# Main.net
KiCad netlist of a schematic drawn in Altium Designer
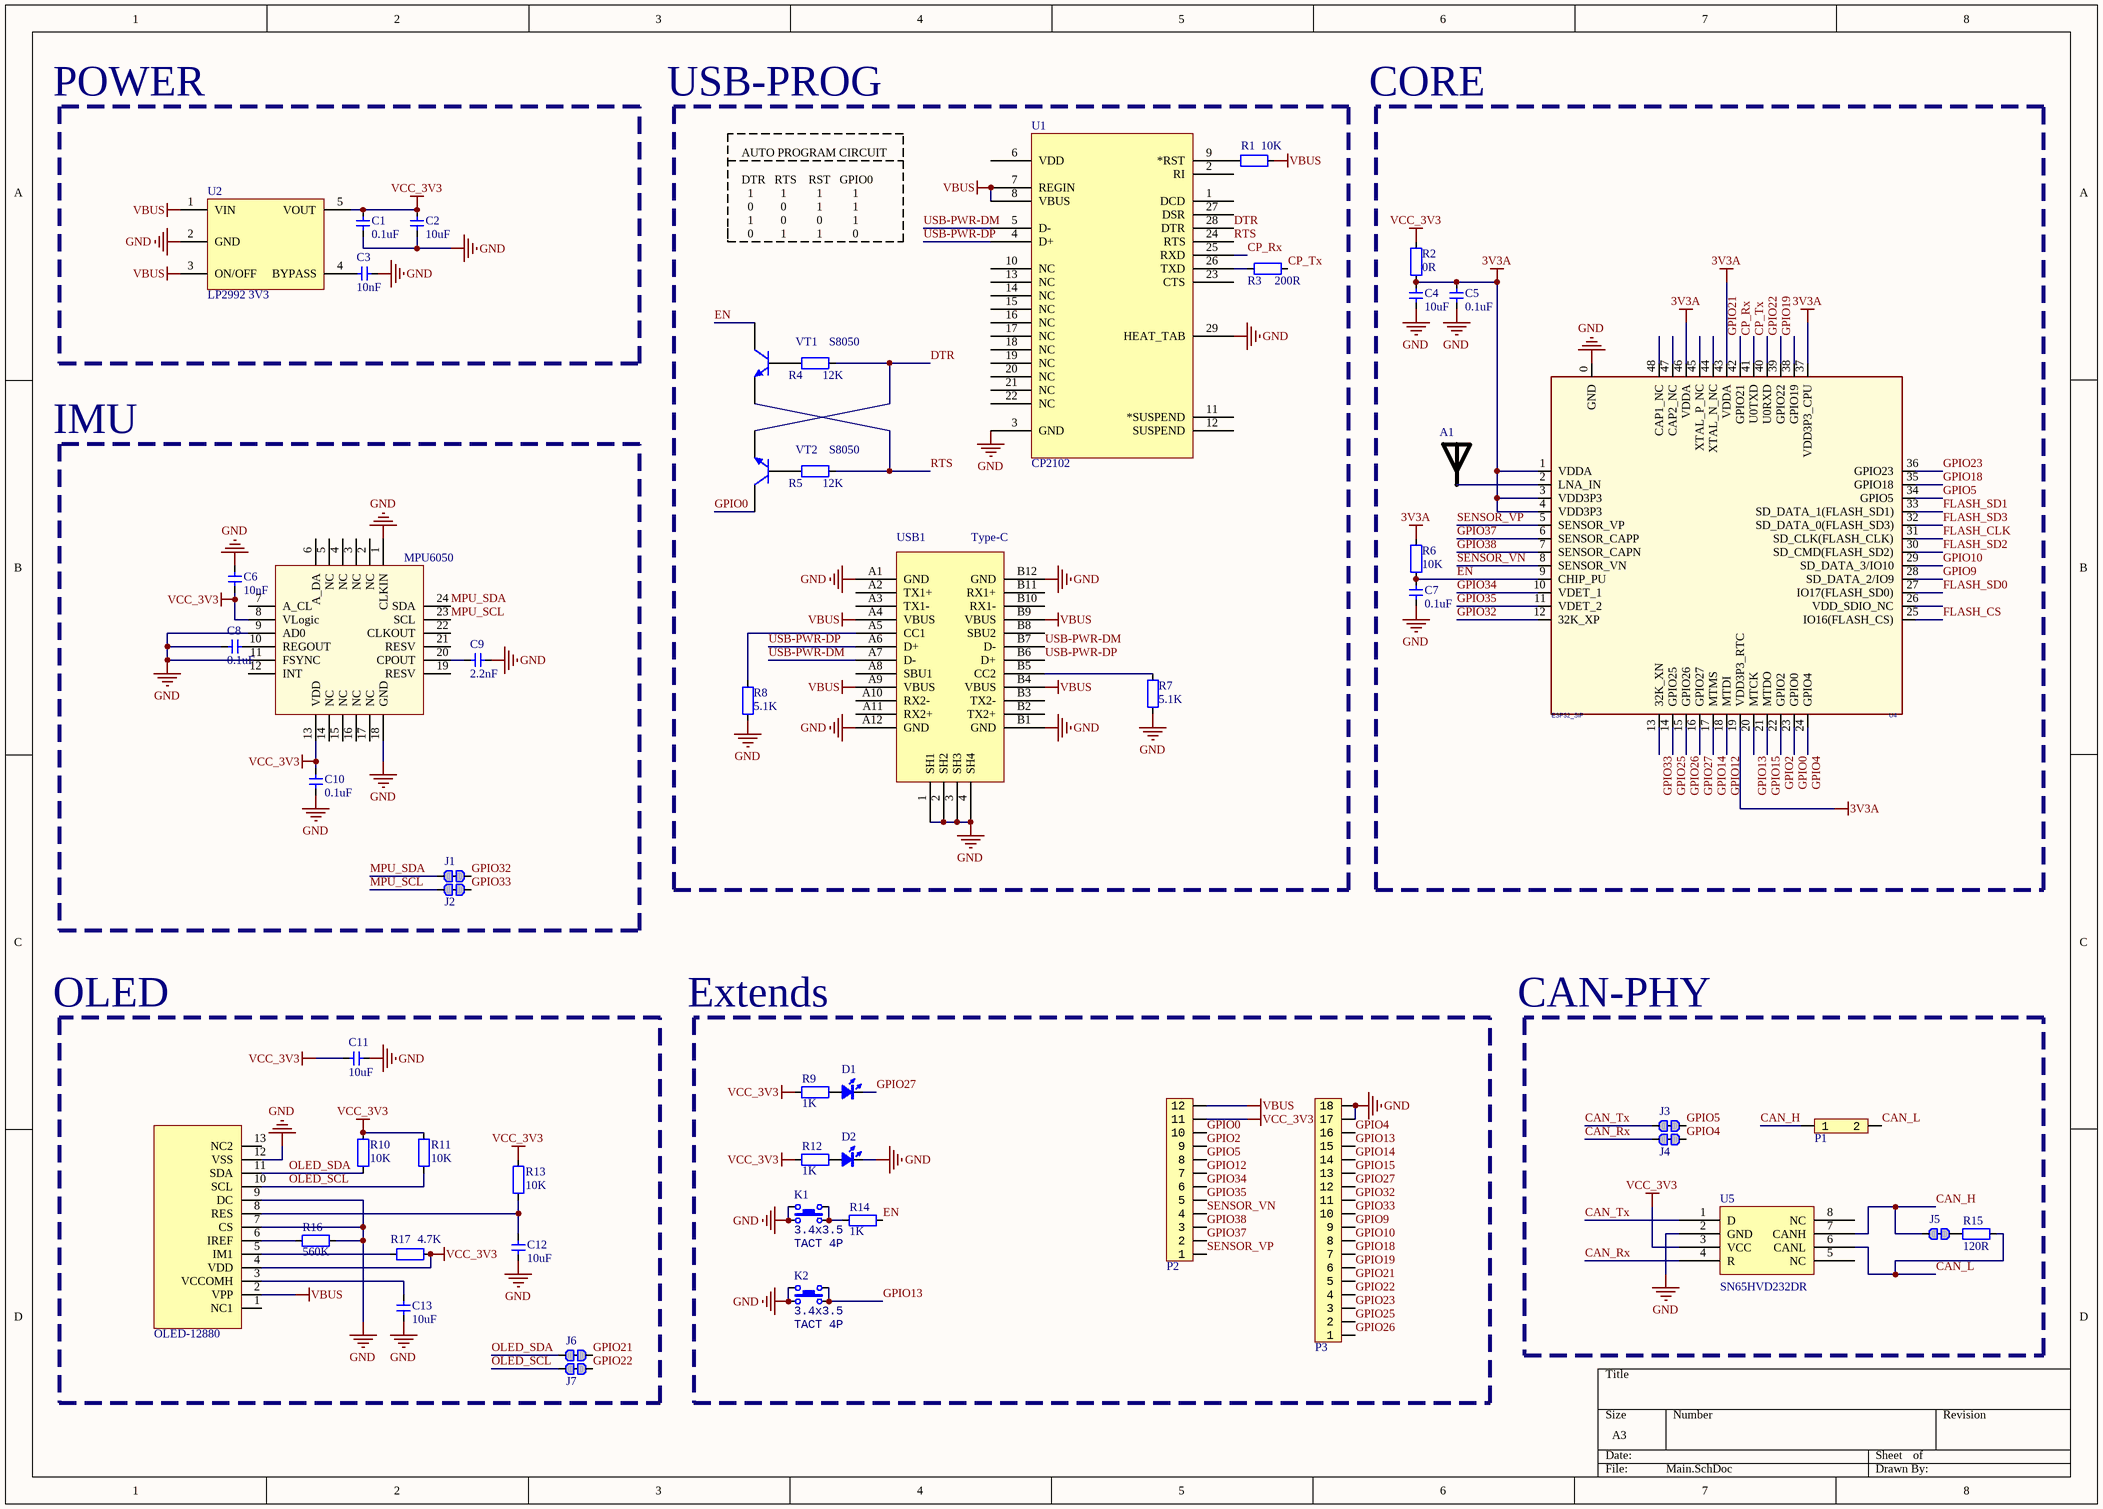
[diagram p0: Main.SchDoc]

(export (version "E")
  (design (tool "Eeschema 10.0.6"))
  (components
    (comp (ref "1")
      (value "OLED-12880")
      (footprint "OLED-12880")
      (libsource (lib "mLib") (part "OLED-12880"))
    )
    (comp (ref "A1")
      (value "RAINSUN")
      (footprint "ANT-Rainsun-AN5120")
      (libsource (lib "MyPcbLib") (part "ANT-Rainsun-AP5120"))
    )
    (comp (ref "C1")
      (value "0.1uF")
      (footprint "CAP_0402")
      (description "Capacitor")
      (libsource (lib "MyPcbLib") (part "电容-0402"))
    )
    (comp (ref "C2")
      (value "10uF")
      (footprint "CAP_0402")
      (description "Capacitor")
      (libsource (lib "MyPcbLib") (part "电容-0402"))
    )
    (comp (ref "C3")
      (value "10nF")
      (footprint "CAP_0402")
      (description "Capacitor")
      (libsource (lib "MyPcbLib") (part "电容-0402"))
    )
    (comp (ref "C4")
      (value "10uF")
      (footprint "CAP_0402")
      (description "Capacitor")
      (libsource (lib "MyPcbLib") (part "电容-0402"))
    )
    (comp (ref "C5")
      (value "0.1uF")
      (footprint "CAP_0402")
      (description "Capacitor")
      (libsource (lib "MyPcbLib") (part "电容-0402"))
    )
    (comp (ref "C6")
      (value "10nF")
      (footprint "CAP_0402")
      (description "Capacitor")
      (libsource (lib "MyPcbLib") (part "电容-0402"))
    )
    (comp (ref "C7")
      (value "0.1uF")
      (footprint "CAP_0402")
      (description "Capacitor")
      (libsource (lib "MyPcbLib") (part "电容-0402"))
    )
    (comp (ref "C8")
      (value "0.1uF")
      (footprint "CAP_0402")
      (description "Capacitor")
      (libsource (lib "MyPcbLib") (part "电容-0402"))
    )
    (comp (ref "C9")
      (value "2.2nF")
      (footprint "CAP_0402")
      (description "Capacitor")
      (libsource (lib "MyPcbLib") (part "电容-0402"))
    )
    (comp (ref "C10")
      (value "0.1uF")
      (footprint "CAP_0402")
      (description "Capacitor")
      (libsource (lib "MyPcbLib") (part "电容-0402"))
    )
    (comp (ref "C11")
      (value "10uF")
      (footprint "CAP_0402")
      (description "Capacitor")
      (libsource (lib "MyPcbLib") (part "电容-0402"))
    )
    (comp (ref "C12")
      (value "10uF")
      (footprint "CAP_0402")
      (description "Capacitor")
      (libsource (lib "MyPcbLib") (part "电容-0402"))
    )
    (comp (ref "C13")
      (value "10uF")
      (footprint "CAP_0402")
      (description "Capacitor")
      (libsource (lib "MyPcbLib") (part "电容-0402"))
    )
    (comp (ref "D1")
      (value "color?")
      (footprint "LED_0402_RED")
      (description "LED")
      (libsource (lib "KitSprout") (part "LED_0402"))
    )
    (comp (ref "D2")
      (value "color?")
      (footprint "LED_0402_RED")
      (description "LED")
      (libsource (lib "KitSprout") (part "LED_0402"))
    )
    (comp (ref "J1")
      (value "跳线")
      (footprint "0402-0R")
      (description "Resistor")
      (fields (field (name "PUBLISHER") "Altium Limited"))
      (libsource (lib "MyPcbLib") (part "跳线"))
    )
    (comp (ref "J2")
      (value "跳线")
      (footprint "0402-0R")
      (description "Resistor")
      (fields (field (name "PUBLISHER") "Altium Limited"))
      (libsource (lib "MyPcbLib") (part "跳线"))
    )
    (comp (ref "J3")
      (value "跳线")
      (footprint "0402-0R")
      (description "Resistor")
      (fields (field (name "PUBLISHER") "Altium Limited"))
      (libsource (lib "MyPcbLib") (part "跳线"))
    )
    (comp (ref "J4")
      (value "跳线")
      (footprint "0402-0R")
      (description "Resistor")
      (fields (field (name "PUBLISHER") "Altium Limited"))
      (libsource (lib "MyPcbLib") (part "跳线"))
    )
    (comp (ref "J5")
      (value "跳线")
      (footprint "0402-0R")
      (description "Resistor")
      (fields (field (name "PUBLISHER") "Altium Limited"))
      (libsource (lib "MyPcbLib") (part "跳线"))
    )
    (comp (ref "J6")
      (value "跳线")
      (footprint "0402-0R")
      (description "Resistor")
      (fields (field (name "PUBLISHER") "Altium Limited"))
      (libsource (lib "MyPcbLib") (part "跳线"))
    )
    (comp (ref "J7")
      (value "跳线")
      (footprint "0402-0R")
      (description "Resistor")
      (fields (field (name "PUBLISHER") "Altium Limited"))
      (libsource (lib "MyPcbLib") (part "跳线"))
    )
    (comp (ref "K1")
      (value "3.4x3.5")
      (footprint "ButtonTACT_3.5*3.55_90")
      (description "Button")
      (fields (field (name "TYPE") "TACT 4P") (field (name "Comment") "TACT 4P"))
      (libsource (lib "KitSprout") (part "ButtonTACT"))
    )
    (comp (ref "K2")
      (value "3.4x3.5")
      (footprint "ButtonTACT_3.5*3.55_90")
      (description "Button")
      (fields (field (name "TYPE") "TACT 4P") (field (name "Comment") "TACT 4P"))
      (libsource (lib "KitSprout") (part "ButtonTACT"))
    )
    (comp (ref "P1")
      (value "HDR2x1_2.54")
      (footprint "HDR1X2_2.54_180")
      (description "Header")
      (libsource (lib "KitSprout") (part "HDR2x1_2.54"))
    )
    (comp (ref "P2")
      (value "HDR1x12_2.54")
      (footprint "HDR1X12_2.54_180")
      (description "Header")
      (libsource (lib "KitSprout") (part "HDR1x12_2.54"))
    )
    (comp (ref "P3")
      (value "HDR1x18_2.54")
      (footprint "HDR1X18_2.54_180")
      (description "Header")
      (libsource (lib "KitSprout") (part "HDR1x18_2.54"))
    )
    (comp (ref "R1")
      (value "10K")
      (footprint "RES_0402")
      (description "Resistor")
      (libsource (lib "") (part "电阻-0402_1"))
    )
    (comp (ref "R2")
      (value "0R")
      (footprint "RES_0402")
      (description "Resistor")
      (libsource (lib "") (part "电阻-0402_2"))
    )
    (comp (ref "R3")
      (value "200R")
      (footprint "RES_0402")
      (description "Resistor")
      (libsource (lib "") (part "电阻-0402_1"))
    )
    (comp (ref "R4")
      (value "12K")
      (footprint "RES_0402")
      (description "Resistor")
      (libsource (lib "") (part "电阻-0402_1"))
    )
    (comp (ref "R5")
      (value "12K")
      (footprint "RES_0402")
      (description "Resistor")
      (libsource (lib "") (part "电阻-0402_1"))
    )
    (comp (ref "R6")
      (value "10K")
      (footprint "RES_0402")
      (description "Resistor")
      (libsource (lib "") (part "电阻-0402_2"))
    )
    (comp (ref "R7")
      (value "5.1K")
      (footprint "RES_0402")
      (description "Resistor")
      (libsource (lib "") (part "电阻-0402_2"))
    )
    (comp (ref "R8")
      (value "5.1K")
      (footprint "RES_0402")
      (description "Resistor")
      (libsource (lib "") (part "电阻-0402_2"))
    )
    (comp (ref "R9")
      (value "1K")
      (footprint "RES_0402")
      (description "Resistor")
      (libsource (lib "MyPcbLib") (part "电阻-0402"))
    )
    (comp (ref "R10")
      (value "10K")
      (footprint "RES_0402")
      (description "Resistor")
      (libsource (lib "") (part "电阻-0402_3"))
    )
    (comp (ref "R11")
      (value "10K")
      (footprint "RES_0402")
      (description "Resistor")
      (libsource (lib "") (part "电阻-0402_3"))
    )
    (comp (ref "R12")
      (value "1K")
      (footprint "RES_0402")
      (description "Resistor")
      (libsource (lib "MyPcbLib") (part "电阻-0402"))
    )
    (comp (ref "R13")
      (value "10K")
      (footprint "RES_0402")
      (description "Resistor")
      (libsource (lib "") (part "电阻-0402_3"))
    )
    (comp (ref "R14")
      (value "1K")
      (footprint "RES_0402")
      (description "Resistor")
      (libsource (lib "MyPcbLib") (part "电阻-0402"))
    )
    (comp (ref "R15")
      (value "120R")
      (footprint "RES_0402")
      (description "Resistor")
      (libsource (lib "MyPcbLib") (part "电阻-0402"))
    )
    (comp (ref "R16")
      (value "560K")
      (footprint "RES_0402")
      (description "Resistor")
      (libsource (lib "MyPcbLib") (part "电阻-0402"))
    )
    (comp (ref "R17")
      (value "4.7K")
      (footprint "RES_0402")
      (description "Resistor")
      (libsource (lib "MyPcbLib") (part "电阻-0402"))
    )
    (comp (ref "U1")
      (value "CP2102")
      (footprint "QFN-28")
      (description "USB转TTL")
      (libsource (lib "mLib") (part "CP2102"))
    )
    (comp (ref "U2")
      (value "LP2992 3V3")
      (footprint "SOT23-5")
      (description "LDO")
      (libsource (lib "MyPcbLib") (part "LP2992"))
    )
    (comp (ref "U3")
      (value "MPU6050")
      (footprint "QFN-24")
      (description "六轴传感器")
      (libsource (lib "mLib") (part "MPU6050"))
    )
    (comp (ref "U4")
      (value "ESP32_SIP")
      (footprint "QFN-48_7X7")
      (libsource (lib "MyPcbLib") (part "ESP32-PICO"))
    )
    (comp (ref "U5")
      (value "SN65HVD232D")
      (footprint "SO-8")
      (fields
        (field (name "MANUFACTURER") "Texas Instruments")
        (field (name "MANUFACTURER PART NUMBER") "SN65HVD232DR")
      )
      (libsource (lib "MyPcbLib") (part "SN65HVD232D"))
    )
    (comp (ref "USB1")
      (value "Type-C")
      (footprint "Type-C-TOP")
      (libsource (lib "MyPcbLib") (part "USB-Type-C-TOP"))
    )
    (comp (ref "VT1")
      (value "S8050")
      (footprint "SMT_TRIODE_NPN")
      (description "Surface mount NPN transistor, package SOT-23")
      (libsource (lib "MyPcbLib") (part "SMT_TRIODE_NPN"))
    )
    (comp (ref "VT2")
      (value "S8050")
      (footprint "SMT_TRIODE_NPN")
      (description "Surface mount NPN transistor, package SOT-23")
      (libsource (lib "MyPcbLib") (part "SMT_TRIODE_NPN"))
    )
  )
  (nets
    (net (code "1") (name "/CAN_H") (class "Default")
      (node (ref "J5") (pin "1") (pinfunction "1_1") (pintype "passive"))
      (node (ref "P1") (pin "1") (pinfunction "1_1") (pintype "passive"))
      (node (ref "U5") (pin "7") (pinfunction "CANH_7") (pintype "passive"))
    )
    (net (code "2") (name "/CAN_L") (class "Default")
      (node (ref "P1") (pin "2") (pinfunction "2_2") (pintype "passive"))
      (node (ref "R15") (pin "2") (pinfunction "2_2") (pintype "passive"))
      (node (ref "U5") (pin "6") (pinfunction "CANL_6") (pintype "passive"))
    )
    (net (code "3") (name "/CAN_Rx") (class "Default")
      (node (ref "J4") (pin "1") (pinfunction "1_1") (pintype "passive"))
      (node (ref "U5") (pin "4") (pinfunction "R_4") (pintype "passive"))
    )
    (net (code "4") (name "/CAN_Tx") (class "Default")
      (node (ref "J3") (pin "1") (pinfunction "1_1") (pintype "passive"))
      (node (ref "U5") (pin "1") (pinfunction "D_1") (pintype "passive"))
    )
    (net (code "5") (name "/CP_Rx") (class "Default")
      (node (ref "U1") (pin "25") (pinfunction "RXD_25") (pintype "passive"))
      (node (ref "U4") (pin "41") (pinfunction "U0TXD_41") (pintype "power_in"))
    )
    (net (code "6") (name "/CP_Tx") (class "Default")
      (node (ref "R3") (pin "1") (pinfunction "1_1") (pintype "passive"))
      (node (ref "U4") (pin "40") (pinfunction "U0RXD_40") (pintype "power_in"))
    )
    (net (code "7") (name "/DTR") (class "Default")
      (node (ref "R4") (pin "1") (pinfunction "1_1") (pintype "passive"))
      (node (ref "U1") (pin "28") (pinfunction "DTR_28") (pintype "passive"))
      (node (ref "VT2") (pin "2") (pinfunction "E_2") (pintype "passive"))
    )
    (net (code "8") (name "/EN") (class "Default")
      (node (ref "C7") (pin "1") (pinfunction "1_1") (pintype "passive"))
      (node (ref "R14") (pin "2") (pinfunction "2_2") (pintype "passive"))
      (node (ref "R6") (pin "2") (pinfunction "2_2") (pintype "passive"))
      (node (ref "U4") (pin "9") (pinfunction "CHIP_PU_9") (pintype "passive"))
      (node (ref "VT1") (pin "3") (pinfunction "C_3") (pintype "passive"))
    )
    (net (code "9") (name "/FLASH_CLK") (class "Default")
      (node (ref "U4") (pin "31") (pinfunction "SD_CLK(FLASH_CLK)_31") (pintype "passive"))
    )
    (net (code "10") (name "/FLASH_CS") (class "Default")
      (node (ref "U4") (pin "25") (pinfunction "IO16(FLASH_CS)_25") (pintype "passive"))
    )
    (net (code "11") (name "/FLASH_SD0") (class "Default")
      (node (ref "U4") (pin "27") (pinfunction "IO17(FLASH_SD0)_27") (pintype "passive"))
    )
    (net (code "12") (name "/FLASH_SD1") (class "Default")
      (node (ref "U4") (pin "33") (pinfunction "SD_DATA_1(FLASH_SD1)_33") (pintype "passive"))
    )
    (net (code "13") (name "/FLASH_SD2") (class "Default")
      (node (ref "U4") (pin "30") (pinfunction "SD_CMD(FLASH_SD2)_30") (pintype "passive"))
    )
    (net (code "14") (name "/FLASH_SD3") (class "Default")
      (node (ref "U4") (pin "32") (pinfunction "SD_DATA_0(FLASH_SD3)_32") (pintype "passive"))
    )
    (net (code "15") (name "/GPIO0") (class "Default")
      (node (ref "P2") (pin "10") (pinfunction "10_10") (pintype "passive"))
      (node (ref "U4") (pin "23") (pinfunction "GPIO0_23") (pintype "passive"))
      (node (ref "VT2") (pin "3") (pinfunction "C_3") (pintype "passive"))
    )
    (net (code "16") (name "/GPIO2") (class "Default")
      (node (ref "P2") (pin "9") (pinfunction "9_9") (pintype "passive"))
      (node (ref "U4") (pin "22") (pinfunction "GPIO2_22") (pintype "passive"))
    )
    (net (code "17") (name "/GPIO4") (class "Default")
      (node (ref "J4") (pin "2") (pinfunction "2_2") (pintype "passive"))
      (node (ref "P3") (pin "16") (pinfunction "16_16") (pintype "passive"))
      (node (ref "U4") (pin "24") (pinfunction "GPIO4_24") (pintype "passive"))
    )
    (net (code "18") (name "/GPIO5") (class "Default")
      (node (ref "J3") (pin "2") (pinfunction "2_2") (pintype "passive"))
      (node (ref "P2") (pin "8") (pinfunction "8_8") (pintype "passive"))
      (node (ref "U4") (pin "34") (pinfunction "GPIO5_34") (pintype "passive"))
    )
    (net (code "19") (name "/GPIO9") (class "Default")
      (node (ref "P3") (pin "9") (pinfunction "9_9") (pintype "passive"))
      (node (ref "U4") (pin "28") (pinfunction "SD_DATA_2/IO9_28") (pintype "passive"))
    )
    (net (code "20") (name "/GPIO10") (class "Default")
      (node (ref "P3") (pin "8") (pinfunction "8_8") (pintype "passive"))
      (node (ref "U4") (pin "29") (pinfunction "SD_DATA_3/IO10_29") (pintype "passive"))
    )
    (net (code "21") (name "/GPIO12") (class "Default")
      (node (ref "P2") (pin "7") (pinfunction "7_7") (pintype "passive"))
      (node (ref "U4") (pin "18") (pinfunction "MTDI_18") (pintype "passive"))
    )
    (net (code "22") (name "/GPIO13") (class "Default")
      (node (ref "K2") (pin "2") (pinfunction "2_2") (pintype "passive"))
      (node (ref "K2") (pin "4") (pinfunction "4_4") (pintype "passive"))
      (node (ref "P3") (pin "15") (pinfunction "15_15") (pintype "passive"))
      (node (ref "U4") (pin "20") (pinfunction "MTCK_20") (pintype "passive"))
    )
    (net (code "23") (name "/GPIO14") (class "Default")
      (node (ref "P3") (pin "14") (pinfunction "14_14") (pintype "passive"))
      (node (ref "U4") (pin "17") (pinfunction "MTMS_17") (pintype "passive"))
    )
    (net (code "24") (name "/GPIO15") (class "Default")
      (node (ref "P3") (pin "13") (pinfunction "13_13") (pintype "passive"))
      (node (ref "U4") (pin "21") (pinfunction "MTDO_21") (pintype "passive"))
    )
    (net (code "25") (name "/GPIO18") (class "Default")
      (node (ref "P3") (pin "7") (pinfunction "7_7") (pintype "passive"))
      (node (ref "U4") (pin "35") (pinfunction "GPIO18_35") (pintype "passive"))
    )
    (net (code "26") (name "/GPIO19") (class "Default")
      (node (ref "P3") (pin "6") (pinfunction "6_6") (pintype "passive"))
      (node (ref "U4") (pin "38") (pinfunction "GPIO19_38") (pintype "passive"))
    )
    (net (code "27") (name "/GPIO21") (class "Default")
      (node (ref "J6") (pin "2") (pinfunction "2_2") (pintype "passive"))
      (node (ref "P3") (pin "5") (pinfunction "5_5") (pintype "passive"))
      (node (ref "U4") (pin "42") (pinfunction "GPIO21_42") (pintype "passive"))
    )
    (net (code "28") (name "/GPIO22") (class "Default")
      (node (ref "J7") (pin "2") (pinfunction "2_2") (pintype "passive"))
      (node (ref "P3") (pin "4") (pinfunction "4_4") (pintype "passive"))
      (node (ref "U4") (pin "39") (pinfunction "GPIO22_39") (pintype "passive"))
    )
    (net (code "29") (name "/GPIO23") (class "Default")
      (node (ref "P3") (pin "3") (pinfunction "3_3") (pintype "passive"))
      (node (ref "U4") (pin "36") (pinfunction "GPIO23_36") (pintype "passive"))
    )
    (net (code "30") (name "/GPIO25") (class "Default")
      (node (ref "P3") (pin "2") (pinfunction "2_2") (pintype "passive"))
      (node (ref "U4") (pin "14") (pinfunction "GPIO25_14") (pintype "passive"))
    )
    (net (code "31") (name "/GPIO26") (class "Default")
      (node (ref "P3") (pin "1") (pinfunction "1_1") (pintype "passive"))
      (node (ref "U4") (pin "15") (pinfunction "GPIO26_15") (pintype "passive"))
    )
    (net (code "32") (name "/GPIO27") (class "Default")
      (node (ref "D1") (pin "2") (pinfunction "K_2") (pintype "passive"))
      (node (ref "P3") (pin "12") (pinfunction "12_12") (pintype "passive"))
      (node (ref "U4") (pin "16") (pinfunction "GPIO27_16") (pintype "passive"))
    )
    (net (code "33") (name "/GPIO32") (class "Default")
      (node (ref "J1") (pin "2") (pinfunction "2_2") (pintype "passive"))
      (node (ref "P3") (pin "11") (pinfunction "11_11") (pintype "passive"))
      (node (ref "U4") (pin "12") (pinfunction "32K_XP_12") (pintype "passive"))
    )
    (net (code "34") (name "/GPIO33") (class "Default")
      (node (ref "J2") (pin "2") (pinfunction "2_2") (pintype "passive"))
      (node (ref "P3") (pin "10") (pinfunction "10_10") (pintype "passive"))
      (node (ref "U4") (pin "13") (pinfunction "32K_XN_13") (pintype "passive"))
    )
    (net (code "35") (name "/GPIO34") (class "Default")
      (node (ref "P2") (pin "6") (pinfunction "6_6") (pintype "passive"))
      (node (ref "U4") (pin "10") (pinfunction "VDET_1_10") (pintype "passive"))
    )
    (net (code "36") (name "/GPIO35") (class "Default")
      (node (ref "P2") (pin "5") (pinfunction "5_5") (pintype "passive"))
      (node (ref "U4") (pin "11") (pinfunction "VDET_2_11") (pintype "passive"))
    )
    (net (code "37") (name "/GPIO37") (class "Default")
      (node (ref "P2") (pin "2") (pinfunction "2_2") (pintype "passive"))
      (node (ref "U4") (pin "6") (pinfunction "SENSOR_CAPP_6") (pintype "passive"))
    )
    (net (code "38") (name "/GPIO38") (class "Default")
      (node (ref "P2") (pin "3") (pinfunction "3_3") (pintype "passive"))
      (node (ref "U4") (pin "7") (pinfunction "SENSOR_CAPN_7") (pintype "passive"))
    )
    (net (code "39") (name "/MPU_SCL") (class "Default")
      (node (ref "J2") (pin "1") (pinfunction "1_1") (pintype "passive"))
      (node (ref "U3") (pin "23") (pinfunction "SCL_23") (pintype "passive"))
    )
    (net (code "40") (name "/MPU_SDA") (class "Default")
      (node (ref "J1") (pin "1") (pinfunction "1_1") (pintype "passive"))
      (node (ref "U3") (pin "24") (pinfunction "SDA_24") (pintype "passive"))
    )
    (net (code "41") (name "/OLED_SCL") (class "Default")
      (node (ref "1") (pin "10") (pinfunction "SCL_10") (pintype "passive"))
      (node (ref "J7") (pin "1") (pinfunction "1_1") (pintype "passive"))
      (node (ref "R11") (pin "1") (pinfunction "1_1") (pintype "passive"))
    )
    (net (code "42") (name "/OLED_SDA") (class "Default")
      (node (ref "1") (pin "11") (pinfunction "SDA_11") (pintype "passive"))
      (node (ref "J6") (pin "1") (pinfunction "1_1") (pintype "passive"))
      (node (ref "R10") (pin "1") (pinfunction "1_1") (pintype "passive"))
    )
    (net (code "43") (name "/RTS") (class "Default")
      (node (ref "R5") (pin "1") (pinfunction "1_1") (pintype "passive"))
      (node (ref "U1") (pin "24") (pinfunction "RTS_24") (pintype "passive"))
      (node (ref "VT1") (pin "2") (pinfunction "E_2") (pintype "passive"))
    )
    (net (code "44") (name "/SENSOR_VN") (class "Default")
      (node (ref "P2") (pin "4") (pinfunction "4_4") (pintype "passive"))
      (node (ref "U4") (pin "8") (pinfunction "SENSOR_VN_8") (pintype "passive"))
    )
    (net (code "45") (name "/SENSOR_VP") (class "Default")
      (node (ref "P2") (pin "1") (pinfunction "1_1") (pintype "passive"))
      (node (ref "U4") (pin "5") (pinfunction "SENSOR_VP_5") (pintype "passive"))
    )
    (net (code "46") (name "/USB-PWR-DM") (class "Default")
      (node (ref "U1") (pin "5") (pinfunction "D-_5") (pintype "passive"))
      (node (ref "USB1") (pin "A7") (pinfunction "D-_A7") (pintype "passive"))
      (node (ref "USB1") (pin "B7") (pinfunction "D-_B7") (pintype "passive"))
    )
    (net (code "47") (name "/USB-PWR-DP") (class "Default")
      (node (ref "U1") (pin "4") (pinfunction "D+_4") (pintype "passive"))
      (node (ref "USB1") (pin "A6") (pinfunction "D+_A6") (pintype "passive"))
      (node (ref "USB1") (pin "B6") (pinfunction "D+_B6") (pintype "passive"))
    )
    (net (code "48") (name "3V3A") (class "Default")
      (node (ref "C4") (pin "2") (pinfunction "2_2") (pintype "passive"))
      (node (ref "C5") (pin "2") (pinfunction "2_2") (pintype "passive"))
      (node (ref "R2") (pin "2") (pinfunction "2_2") (pintype "passive"))
      (node (ref "R6") (pin "1") (pinfunction "1_1") (pintype "passive"))
      (node (ref "U4") (pin "1") (pinfunction "VDDA_1") (pintype "power_in"))
      (node (ref "U4") (pin "19") (pinfunction "VDD3P3_RTC_19") (pintype "power_in"))
      (node (ref "U4") (pin "3") (pinfunction "VDD3P3_3") (pintype "power_in"))
      (node (ref "U4") (pin "37") (pinfunction "VDD3P3_CPU_37") (pintype "power_in"))
      (node (ref "U4") (pin "4") (pinfunction "VDD3P3_4") (pintype "power_in"))
      (node (ref "U4") (pin "43") (pinfunction "VDDA_43") (pintype "power_in"))
      (node (ref "U4") (pin "46") (pinfunction "VDDA_46") (pintype "power_in"))
    )
    (net (code "49") (name "GND") (class "Default")
      (node (ref "1") (pin "12") (pinfunction "VSS_12") (pintype "passive"))
      (node (ref "1") (pin "7") (pinfunction "CS_7") (pintype "passive"))
      (node (ref "1") (pin "9") (pinfunction "DC_9") (pintype "passive"))
      (node (ref "C1") (pin "1") (pinfunction "1_1") (pintype "passive"))
      (node (ref "C10") (pin "1") (pinfunction "1_1") (pintype "passive"))
      (node (ref "C11") (pin "1") (pinfunction "1_1") (pintype "passive"))
      (node (ref "C12") (pin "1") (pinfunction "1_1") (pintype "passive"))
      (node (ref "C13") (pin "1") (pinfunction "1_1") (pintype "passive"))
      (node (ref "C2") (pin "1") (pinfunction "1_1") (pintype "passive"))
      (node (ref "C3") (pin "1") (pinfunction "1_1") (pintype "passive"))
      (node (ref "C4") (pin "1") (pinfunction "1_1") (pintype "passive"))
      (node (ref "C5") (pin "1") (pinfunction "1_1") (pintype "passive"))
      (node (ref "C6") (pin "2") (pinfunction "2_2") (pintype "passive"))
      (node (ref "C7") (pin "2") (pinfunction "2_2") (pintype "passive"))
      (node (ref "C8") (pin "2") (pinfunction "2_2") (pintype "passive"))
      (node (ref "C9") (pin "1") (pinfunction "1_1") (pintype "passive"))
      (node (ref "D2") (pin "2") (pinfunction "K_2") (pintype "passive"))
      (node (ref "K1") (pin "1") (pinfunction "1_1") (pintype "passive"))
      (node (ref "K1") (pin "3") (pinfunction "3_3") (pintype "passive"))
      (node (ref "K2") (pin "1") (pinfunction "1_1") (pintype "passive"))
      (node (ref "K2") (pin "3") (pinfunction "3_3") (pintype "passive"))
      (node (ref "P3") (pin "17") (pinfunction "17_17") (pintype "passive"))
      (node (ref "P3") (pin "18") (pinfunction "18_18") (pintype "passive"))
      (node (ref "R16") (pin "2") (pinfunction "2_2") (pintype "passive"))
      (node (ref "R7") (pin "2") (pinfunction "2_2") (pintype "passive"))
      (node (ref "R8") (pin "2") (pinfunction "2_2") (pintype "passive"))
      (node (ref "U1") (pin "29") (pinfunction "HEAT_TAB_29") (pintype "passive"))
      (node (ref "U1") (pin "3") (pinfunction "GND_3") (pintype "passive"))
      (node (ref "U2") (pin "2") (pinfunction "GND_2") (pintype "passive"))
      (node (ref "U3") (pin "1") (pinfunction "CLKIN_1") (pintype "passive"))
      (node (ref "U3") (pin "11") (pinfunction "FSYNC_11") (pintype "passive"))
      (node (ref "U3") (pin "18") (pinfunction "GND_18") (pintype "passive"))
      (node (ref "U3") (pin "9") (pinfunction "AD0_9") (pintype "passive"))
      (node (ref "U4") (pin "0") (pinfunction "GND_0") (pintype "power_in"))
      (node (ref "U5") (pin "2") (pinfunction "GND_2") (pintype "passive"))
      (node (ref "USB1") (pin "1") (pinfunction "SH1_1") (pintype "passive"))
      (node (ref "USB1") (pin "2") (pinfunction "SH2_2") (pintype "passive"))
      (node (ref "USB1") (pin "3") (pinfunction "SH3_3") (pintype "passive"))
      (node (ref "USB1") (pin "4") (pinfunction "SH4_4") (pintype "passive"))
      (node (ref "USB1") (pin "A1") (pinfunction "GND_A1") (pintype "passive"))
      (node (ref "USB1") (pin "A12") (pinfunction "GND_A12") (pintype "passive"))
      (node (ref "USB1") (pin "B1") (pinfunction "GND_B1") (pintype "passive"))
      (node (ref "USB1") (pin "B12") (pinfunction "GND_B12") (pintype "passive"))
    )
    (net (code "50") (name "Net-(1-IM1)") (class "Default")
      (node (ref "1") (pin "5") (pinfunction "IM1_5") (pintype "passive"))
      (node (ref "R17") (pin "1") (pinfunction "1_1") (pintype "passive"))
    )
    (net (code "51") (name "Net-(1-IREF)") (class "Default")
      (node (ref "1") (pin "6") (pinfunction "IREF_6") (pintype "passive"))
      (node (ref "R16") (pin "1") (pinfunction "1_1") (pintype "passive"))
    )
    (net (code "52") (name "Net-(1-RES)") (class "Default")
      (node (ref "1") (pin "8") (pinfunction "RES_8") (pintype "passive"))
      (node (ref "C12") (pin "2") (pinfunction "2_2") (pintype "passive"))
      (node (ref "R13") (pin "1") (pinfunction "1_1") (pintype "passive"))
    )
    (net (code "53") (name "Net-(1-VCCOMH)") (class "Default")
      (node (ref "1") (pin "3") (pinfunction "VCCOMH_3") (pintype "passive"))
      (node (ref "C13") (pin "2") (pinfunction "2_2") (pintype "passive"))
    )
    (net (code "54") (name "Net-(D1-A)") (class "Default")
      (node (ref "D1") (pin "1") (pinfunction "A_1") (pintype "passive"))
      (node (ref "R9") (pin "2") (pinfunction "2_2") (pintype "passive"))
    )
    (net (code "55") (name "Net-(D2-A)") (class "Default")
      (node (ref "D2") (pin "1") (pinfunction "A_1") (pintype "passive"))
      (node (ref "R12") (pin "2") (pinfunction "2_2") (pintype "passive"))
    )
    (net (code "56") (name "Net-(J5-Pad2)") (class "Default")
      (node (ref "J5") (pin "2") (pinfunction "2_2") (pintype "passive"))
      (node (ref "R15") (pin "1") (pinfunction "1_1") (pintype "passive"))
    )
    (net (code "57") (name "Net-(K1-Pad2)") (class "Default")
      (node (ref "K1") (pin "2") (pinfunction "2_2") (pintype "passive"))
      (node (ref "K1") (pin "4") (pinfunction "4_4") (pintype "passive"))
      (node (ref "R14") (pin "1") (pinfunction "1_1") (pintype "passive"))
    )
    (net (code "58") (name "Net-(U1-*RST)") (class "Default")
      (node (ref "R1") (pin "2") (pinfunction "2_2") (pintype "passive"))
      (node (ref "U1") (pin "9") (pinfunction "*RST_9") (pintype "passive"))
    )
    (net (code "59") (name "Net-(U1-TXD)") (class "Default")
      (node (ref "R3") (pin "2") (pinfunction "2_2") (pintype "passive"))
      (node (ref "U1") (pin "26") (pinfunction "TXD_26") (pintype "passive"))
    )
    (net (code "60") (name "Net-(U2-BYPASS)") (class "Default")
      (node (ref "C3") (pin "2") (pinfunction "2_2") (pintype "passive"))
      (node (ref "U2") (pin "4") (pinfunction "BYPASS_4") (pintype "passive"))
    )
    (net (code "61") (name "Net-(U3-CPOUT)") (class "Default")
      (node (ref "C9") (pin "2") (pinfunction "2_2") (pintype "passive"))
      (node (ref "U3") (pin "20") (pinfunction "CPOUT_20") (pintype "passive"))
    )
    (net (code "62") (name "Net-(U3-REGOUT)") (class "Default")
      (node (ref "C8") (pin "1") (pinfunction "1_1") (pintype "passive"))
      (node (ref "U3") (pin "10") (pinfunction "REGOUT_10") (pintype "passive"))
    )
    (net (code "63") (name "Net-(U4-LNA_IN)") (class "Default")
      (node (ref "A1") (pin "1") (pinfunction "1_1") (pintype "passive"))
      (node (ref "U4") (pin "2") (pinfunction "LNA_IN_2") (pintype "passive"))
    )
    (net (code "64") (name "Net-(USB1-CC1)") (class "Default")
      (node (ref "R8") (pin "1") (pinfunction "1_1") (pintype "passive"))
      (node (ref "USB1") (pin "A5") (pinfunction "CC1_A5") (pintype "passive"))
    )
    (net (code "65") (name "Net-(USB1-CC2)") (class "Default")
      (node (ref "R7") (pin "1") (pinfunction "1_1") (pintype "passive"))
      (node (ref "USB1") (pin "B5") (pinfunction "CC2_B5") (pintype "passive"))
    )
    (net (code "66") (name "Net-(VT1-B)") (class "Default")
      (node (ref "R4") (pin "2") (pinfunction "2_2") (pintype "passive"))
      (node (ref "VT1") (pin "1") (pinfunction "B_1") (pintype "passive"))
    )
    (net (code "67") (name "Net-(VT2-B)") (class "Default")
      (node (ref "R5") (pin "2") (pinfunction "2_2") (pintype "passive"))
      (node (ref "VT2") (pin "1") (pinfunction "B_1") (pintype "passive"))
    )
    (net (code "68") (name "VBUS") (class "Default")
      (node (ref "1") (pin "2") (pinfunction "VPP_2") (pintype "passive"))
      (node (ref "P2") (pin "12") (pinfunction "12_12") (pintype "passive"))
      (node (ref "R1") (pin "1") (pinfunction "1_1") (pintype "passive"))
      (node (ref "U1") (pin "7") (pinfunction "REGIN_7") (pintype "passive"))
      (node (ref "U1") (pin "8") (pinfunction "VBUS_8") (pintype "passive"))
      (node (ref "U2") (pin "1") (pinfunction "VIN_1") (pintype "passive"))
      (node (ref "U2") (pin "3") (pinfunction "ON/OFF_3") (pintype "passive"))
      (node (ref "USB1") (pin "A4") (pinfunction "VBUS_A4") (pintype "passive"))
      (node (ref "USB1") (pin "A9") (pinfunction "VBUS_A9") (pintype "passive"))
      (node (ref "USB1") (pin "B4") (pinfunction "VBUS_B4") (pintype "passive"))
      (node (ref "USB1") (pin "B9") (pinfunction "VBUS_B9") (pintype "passive"))
    )
    (net (code "69") (name "VCC_3V3") (class "Default")
      (node (ref "1") (pin "4") (pinfunction "VDD_4") (pintype "passive"))
      (node (ref "C1") (pin "2") (pinfunction "2_2") (pintype "passive"))
      (node (ref "C10") (pin "2") (pinfunction "2_2") (pintype "passive"))
      (node (ref "C11") (pin "2") (pinfunction "2_2") (pintype "passive"))
      (node (ref "C2") (pin "2") (pinfunction "2_2") (pintype "passive"))
      (node (ref "C6") (pin "1") (pinfunction "1_1") (pintype "passive"))
      (node (ref "P2") (pin "11") (pinfunction "11_11") (pintype "passive"))
      (node (ref "R10") (pin "2") (pinfunction "2_2") (pintype "passive"))
      (node (ref "R11") (pin "2") (pinfunction "2_2") (pintype "passive"))
      (node (ref "R12") (pin "1") (pinfunction "1_1") (pintype "passive"))
      (node (ref "R13") (pin "2") (pinfunction "2_2") (pintype "passive"))
      (node (ref "R17") (pin "2") (pinfunction "2_2") (pintype "passive"))
      (node (ref "R2") (pin "1") (pinfunction "1_1") (pintype "passive"))
      (node (ref "R9") (pin "1") (pinfunction "1_1") (pintype "passive"))
      (node (ref "U2") (pin "5") (pinfunction "VOUT_5") (pintype "passive"))
      (node (ref "U3") (pin "13") (pinfunction "VDD_13") (pintype "passive"))
      (node (ref "U3") (pin "8") (pinfunction "VLogic_8") (pintype "passive"))
      (node (ref "U5") (pin "3") (pinfunction "VCC_3") (pintype "passive"))
    )
    (net (code "70") (name "unconnected-(1-NC1-Pad1)") (class "Default")
      (node (ref "1") (pin "1") (pinfunction "NC1_1") (pintype "passive"))
    )
    (net (code "71") (name "unconnected-(1-NC2-Pad13)") (class "Default")
      (node (ref "1") (pin "13") (pinfunction "NC2_13") (pintype "passive"))
    )
    (net (code "72") (name "unconnected-(U1-*SUSPEND-Pad11)") (class "Default")
      (node (ref "U1") (pin "11") (pinfunction "*SUSPEND_11") (pintype "passive"))
    )
    (net (code "73") (name "unconnected-(U1-CTS-Pad23)") (class "Default")
      (node (ref "U1") (pin "23") (pinfunction "CTS_23") (pintype "passive"))
    )
    (net (code "74") (name "unconnected-(U1-DCD-Pad1)") (class "Default")
      (node (ref "U1") (pin "1") (pinfunction "DCD_1") (pintype "passive"))
    )
    (net (code "75") (name "unconnected-(U1-DSR-Pad27)") (class "Default")
      (node (ref "U1") (pin "27") (pinfunction "DSR_27") (pintype "passive"))
    )
    (net (code "76") (name "unconnected-(U1-NC-Pad10)") (class "Default")
      (node (ref "U1") (pin "10") (pinfunction "NC_10") (pintype "passive"))
    )
    (net (code "77") (name "unconnected-(U1-NC-Pad13)") (class "Default")
      (node (ref "U1") (pin "13") (pinfunction "NC_13") (pintype "passive"))
    )
    (net (code "78") (name "unconnected-(U1-NC-Pad14)") (class "Default")
      (node (ref "U1") (pin "14") (pinfunction "NC_14") (pintype "passive"))
    )
    (net (code "79") (name "unconnected-(U1-NC-Pad15)") (class "Default")
      (node (ref "U1") (pin "15") (pinfunction "NC_15") (pintype "passive"))
    )
    (net (code "80") (name "unconnected-(U1-NC-Pad16)") (class "Default")
      (node (ref "U1") (pin "16") (pinfunction "NC_16") (pintype "passive"))
    )
    (net (code "81") (name "unconnected-(U1-NC-Pad17)") (class "Default")
      (node (ref "U1") (pin "17") (pinfunction "NC_17") (pintype "passive"))
    )
    (net (code "82") (name "unconnected-(U1-NC-Pad18)") (class "Default")
      (node (ref "U1") (pin "18") (pinfunction "NC_18") (pintype "passive"))
    )
    (net (code "83") (name "unconnected-(U1-NC-Pad19)") (class "Default")
      (node (ref "U1") (pin "19") (pinfunction "NC_19") (pintype "passive"))
    )
    (net (code "84") (name "unconnected-(U1-NC-Pad20)") (class "Default")
      (node (ref "U1") (pin "20") (pinfunction "NC_20") (pintype "passive"))
    )
    (net (code "85") (name "unconnected-(U1-NC-Pad21)") (class "Default")
      (node (ref "U1") (pin "21") (pinfunction "NC_21") (pintype "passive"))
    )
    (net (code "86") (name "unconnected-(U1-NC-Pad22)") (class "Default")
      (node (ref "U1") (pin "22") (pinfunction "NC_22") (pintype "passive"))
    )
    (net (code "87") (name "unconnected-(U1-RI-Pad2)") (class "Default")
      (node (ref "U1") (pin "2") (pinfunction "RI_2") (pintype "passive"))
    )
    (net (code "88") (name "unconnected-(U1-SUSPEND-Pad12)") (class "Default")
      (node (ref "U1") (pin "12") (pinfunction "SUSPEND_12") (pintype "passive"))
    )
    (net (code "89") (name "unconnected-(U1-VDD-Pad6)") (class "Default")
      (node (ref "U1") (pin "6") (pinfunction "VDD_6") (pintype "passive"))
    )
    (net (code "90") (name "unconnected-(U3-A_CL-Pad7)") (class "Default")
      (node (ref "U3") (pin "7") (pinfunction "A_CL_7") (pintype "passive"))
    )
    (net (code "91") (name "unconnected-(U3-A_DA-Pad6)") (class "Default")
      (node (ref "U3") (pin "6") (pinfunction "A_DA_6") (pintype "passive"))
    )
    (net (code "92") (name "unconnected-(U3-CLKOUT-Pad22)") (class "Default")
      (node (ref "U3") (pin "22") (pinfunction "CLKOUT_22") (pintype "passive"))
    )
    (net (code "93") (name "unconnected-(U3-INT-Pad12)") (class "Default")
      (node (ref "U3") (pin "12") (pinfunction "INT_12") (pintype "passive"))
    )
    (net (code "94") (name "unconnected-(U3-NC-Pad2)") (class "Default")
      (node (ref "U3") (pin "2") (pinfunction "NC_2") (pintype "passive"))
    )
    (net (code "95") (name "unconnected-(U3-NC-Pad3)") (class "Default")
      (node (ref "U3") (pin "3") (pinfunction "NC_3") (pintype "passive"))
    )
    (net (code "96") (name "unconnected-(U3-NC-Pad4)") (class "Default")
      (node (ref "U3") (pin "4") (pinfunction "NC_4") (pintype "passive"))
    )
    (net (code "97") (name "unconnected-(U3-NC-Pad5)") (class "Default")
      (node (ref "U3") (pin "5") (pinfunction "NC_5") (pintype "passive"))
    )
    (net (code "98") (name "unconnected-(U3-NC-Pad14)") (class "Default")
      (node (ref "U3") (pin "14") (pinfunction "NC_14") (pintype "passive"))
    )
    (net (code "99") (name "unconnected-(U3-NC-Pad15)") (class "Default")
      (node (ref "U3") (pin "15") (pinfunction "NC_15") (pintype "passive"))
    )
    (net (code "100") (name "unconnected-(U3-NC-Pad16)") (class "Default")
      (node (ref "U3") (pin "16") (pinfunction "NC_16") (pintype "passive"))
    )
    (net (code "101") (name "unconnected-(U3-NC-Pad17)") (class "Default")
      (node (ref "U3") (pin "17") (pinfunction "NC_17") (pintype "passive"))
    )
    (net (code "102") (name "unconnected-(U3-RESV-Pad19)") (class "Default")
      (node (ref "U3") (pin "19") (pinfunction "RESV_19") (pintype "passive"))
    )
    (net (code "103") (name "unconnected-(U3-RESV-Pad21)") (class "Default")
      (node (ref "U3") (pin "21") (pinfunction "RESV_21") (pintype "passive"))
    )
    (net (code "104") (name "unconnected-(U4-CAP1_NC-Pad48)") (class "Default")
      (node (ref "U4") (pin "48") (pinfunction "CAP1_NC_48") (pintype "passive"))
    )
    (net (code "105") (name "unconnected-(U4-CAP2_NC-Pad47)") (class "Default")
      (node (ref "U4") (pin "47") (pinfunction "CAP2_NC_47") (pintype "passive"))
    )
    (net (code "106") (name "unconnected-(U4-VDD_SDIO_NC-Pad26)") (class "Default")
      (node (ref "U4") (pin "26") (pinfunction "VDD_SDIO_NC_26") (pintype "passive"))
    )
    (net (code "107") (name "unconnected-(U4-XTAL_N_NC-Pad44)") (class "Default")
      (node (ref "U4") (pin "44") (pinfunction "XTAL_N_NC_44") (pintype "passive"))
    )
    (net (code "108") (name "unconnected-(U4-XTAL_P_NC-Pad45)") (class "Default")
      (node (ref "U4") (pin "45") (pinfunction "XTAL_P_NC_45") (pintype "passive"))
    )
    (net (code "109") (name "unconnected-(U5-NC-Pad5)") (class "Default")
      (node (ref "U5") (pin "5") (pinfunction "NC_5") (pintype "passive"))
    )
    (net (code "110") (name "unconnected-(U5-NC-Pad8)") (class "Default")
      (node (ref "U5") (pin "8") (pinfunction "NC_8") (pintype "passive"))
    )
    (net (code "111") (name "unconnected-(USB1-RX1+-PadB11)") (class "Default")
      (node (ref "USB1") (pin "B11") (pinfunction "RX1+_B11") (pintype "passive"))
    )
    (net (code "112") (name "unconnected-(USB1-RX1--PadB10)") (class "Default")
      (node (ref "USB1") (pin "B10") (pinfunction "RX1-_B10") (pintype "passive"))
    )
    (net (code "113") (name "unconnected-(USB1-RX2+-PadA11)") (class "Default")
      (node (ref "USB1") (pin "A11") (pinfunction "RX2+_A11") (pintype "passive"))
    )
    (net (code "114") (name "unconnected-(USB1-RX2--PadA10)") (class "Default")
      (node (ref "USB1") (pin "A10") (pinfunction "RX2-_A10") (pintype "passive"))
    )
    (net (code "115") (name "unconnected-(USB1-SBU1-PadA8)") (class "Default")
      (node (ref "USB1") (pin "A8") (pinfunction "SBU1_A8") (pintype "passive"))
    )
    (net (code "116") (name "unconnected-(USB1-SBU2-PadB8)") (class "Default")
      (node (ref "USB1") (pin "B8") (pinfunction "SBU2_B8") (pintype "passive"))
    )
    (net (code "117") (name "unconnected-(USB1-TX1+-PadA2)") (class "Default")
      (node (ref "USB1") (pin "A2") (pinfunction "TX1+_A2") (pintype "passive"))
    )
    (net (code "118") (name "unconnected-(USB1-TX1--PadA3)") (class "Default")
      (node (ref "USB1") (pin "A3") (pinfunction "TX1-_A3") (pintype "passive"))
    )
    (net (code "119") (name "unconnected-(USB1-TX2+-PadB2)") (class "Default")
      (node (ref "USB1") (pin "B2") (pinfunction "TX2+_B2") (pintype "passive"))
    )
    (net (code "120") (name "unconnected-(USB1-TX2--PadB3)") (class "Default")
      (node (ref "USB1") (pin "B3") (pinfunction "TX2-_B3") (pintype "passive"))
    )
  )
)
